# H16R7x_Backend.net
KiCad netlist of a schematic drawn in Altium Designer
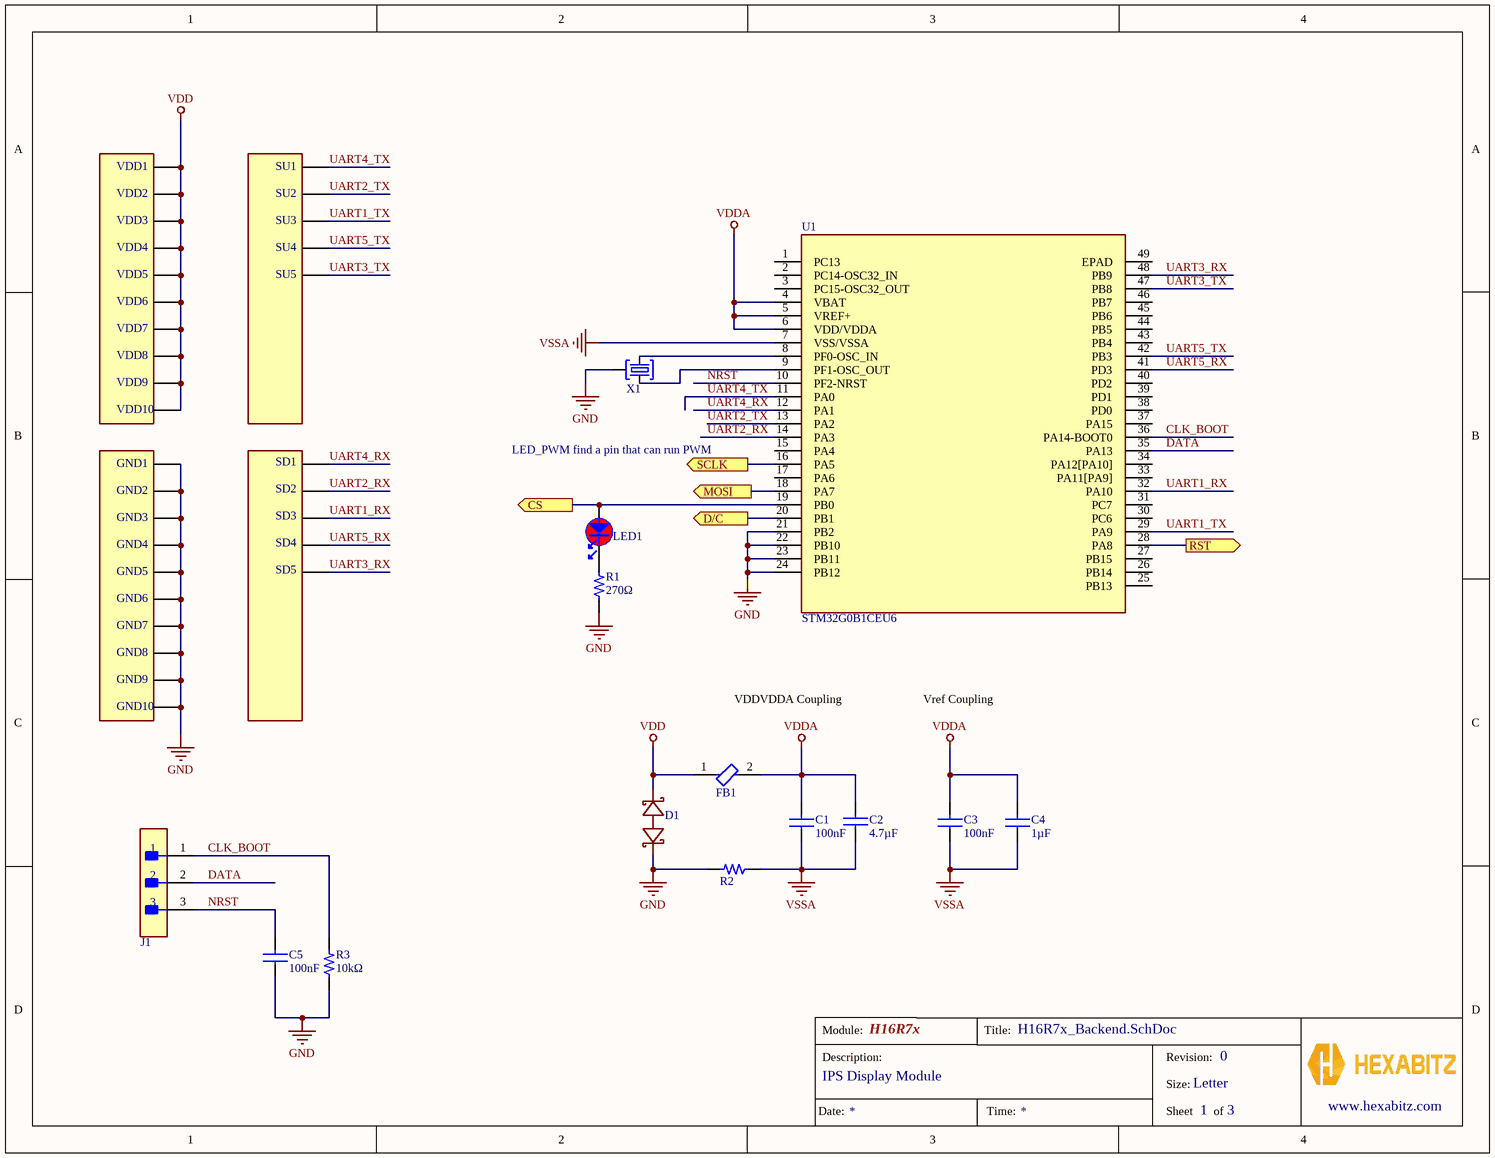
[diagram p0: H16R7x_Backend.SchDoc]

(export (version "E")
  (design (tool "Eeschema 10.0.6"))
  (components
    (comp (ref "C1")
      (value "100nF")
      (footprint "C0603")
      (fields
        (field (name "MANUFACTURER") "Samsung Electro-Mechanics")
        (field (name "MANUFACTURER PART NUMBER") "CL10B104KA8NNNC")
        (field (name "TOLERANCE") "10%")
      )
      (libsource (lib "Hexabitz Altium Library") (part "generic Capacitor"))
    )
    (comp (ref "C2")
      (value "4.7µF")
      (footprint "C0805")
      (fields
        (field (name "MANUFACTURER") "Samsung Electro-Mechanics")
        (field (name "MANUFACTURER PART NUMBER") "CL21X475KAQNNNE")
        (field (name "TOLERANCE") "10%")
      )
      (libsource (lib "Hexabitz Altium Library") (part "generic Capacitor"))
    )
    (comp (ref "C3")
      (value "100nF")
      (footprint "C0603")
      (fields
        (field (name "MANUFACTURER") "Samsung Electro-Mechanics")
        (field (name "MANUFACTURER PART NUMBER") "CL10B104KA8NNNC")
        (field (name "TOLERANCE") "10%")
      )
      (libsource (lib "Hexabitz Altium Library") (part "generic Capacitor"))
    )
    (comp (ref "C4")
      (value "1µF")
      (footprint "C0805")
      (description "Ceramic Capacitor, Ceramic, 16V, 10% +Tol, 10% -Tol, X7R, 15% TC, 1uF, Surface Mount, 0805")
      (fields
        (field (name "MANUFACTURER") "Yageo Group")
        (field (name "MANUFACTURER PART NUMBER") "CC0805KKX7R7BB105")
      )
      (libsource (lib "Hexabitz Altium Library") (part "generic Capacitor"))
    )
    (comp (ref "C5")
      (value "100nF")
      (footprint "C0603")
      (fields
        (field (name "MANUFACTURER") "Samsung Electro-Mechanics")
        (field (name "MANUFACTURER PART NUMBER") "CL10B104KA8NNNC")
        (field (name "TOLERANCE") "10%")
      )
      (libsource (lib "Hexabitz Altium Library") (part "generic Capacitor"))
    )
    (comp (ref "D1")
      (value "CDSOD323-T03SC")
      (footprint "SOD2513X114N")
      (description "A 3V, 350W, bi-directional, standard capacitance, SOD323 pkg TVS Diode ¦ Bourns CDSOD323-T03SC")
      (fields (field (name "MANUFACTURER") "Bourns"))
      (libsource (lib "Hexabitz Altium Library") (part "CDSOD323-T03SC"))
    )
    (comp (ref "FB1")
      (value "MMZ1608Y300B")
      (footprint "FP-MMZ1608-0_8-MFG")
      (description "Ferrite Beads 0603 30ohms 1500mA Signal Line AEC-Q200")
      (fields
        (field (name "MANUFACTURER") "TDK")
        (field (name "MANUFACTURER PART NUMBER") "MMZ1608Y300BTD25")
      )
      (libsource (lib "Hexabitz Altium Library") (part "MMZ1608Y300B"))
    )
    (comp (ref "GND1")
      (value "HEXABIT_UART_PORT")
      (footprint "HEXABIT_POWER_PORT_D")
      (libsource (lib "hexabitz_connectors.Library") (part "HEXABIT_POWER_PORT_D"))
    )
    (comp (ref "GND2")
      (value "HEXABIT_UART_PORT")
      (footprint "HEXABIT_POWER_PORT_D")
      (libsource (lib "hexabitz_connectors.Library") (part "HEXABIT_POWER_PORT_D"))
    )
    (comp (ref "GND3")
      (value "HEXABIT_UART_PORT")
      (footprint "HEXABIT_POWER_PORT_D_300R")
      (libsource (lib "hexabitz_connectors.Library") (part "HEXABIT_POWER_PORT_D_300R"))
    )
    (comp (ref "GND4")
      (value "HEXABIT_UART_PORT")
      (footprint "HEXABIT_POWER_PORT_D")
      (libsource (lib "hexabitz_connectors.Library") (part "HEXABIT_POWER_PORT_D"))
    )
    (comp (ref "GND5")
      (value "HEXABIT_UART_PORT")
      (footprint "HEXABIT_POWER_PORT_D")
      (libsource (lib "hexabitz_connectors.Library") (part "HEXABIT_POWER_PORT_D"))
    )
    (comp (ref "GND6")
      (value "HEXABIT_UART_PORT")
      (footprint "HEXABIT_POWER_PORT_D")
      (libsource (lib "hexabitz_connectors.Library") (part "HEXABIT_POWER_PORT_D"))
    )
    (comp (ref "GND7")
      (value "HEXABIT_UART_PORT")
      (footprint "HEXABIT_POWER_PORT_D")
      (libsource (lib "hexabitz_connectors.Library") (part "HEXABIT_POWER_PORT_D"))
    )
    (comp (ref "GND8")
      (value "HEXABIT_UART_PORT")
      (footprint "HEXABIT_POWER_PORT_D_300L")
      (libsource (lib "hexabitz_connectors.Library") (part "HEXABIT_POWER_PORT_D_300L"))
    )
    (comp (ref "GND9")
      (value "HEXABIT_UART_PORT")
      (footprint "HEXABIT_POWER_PORT_D")
      (libsource (lib "hexabitz_connectors.Library") (part "HEXABIT_POWER_PORT_D"))
    )
    (comp (ref "GND10")
      (value "HEXABIT_UART_PORT")
      (footprint "HEXABIT_POWER_PORT_D")
      (libsource (lib "hexabitz_connectors.Library") (part "HEXABIT_POWER_PORT_D"))
    )
    (comp (ref "J1")
      (value "TSW-103-14-G-S")
      (footprint "FP-TSW-103-14-G-S-MFG")
      (description "CONN HEADER VERT 3POS 2.54MM")
      (libsource (lib "Altium Content Vault") (part "cd3439d6ef35ae5d9b27ec4fdd3e828"))
    )
    (comp (ref "LED1")
      (value "VLMS1300-GS08")
      (footprint "FP-6_541-5092_01-4-MFG")
      (description "LED Uni-Color Super Red 639nm 2-Pin Chip 0603(1608Metric) T/R")
      (fields (field (name "MANUFACTURER") "Vishay Semiconductors"))
      (libsource (lib "Hexabitz Altium Library") (part "VLMS1300-GS08"))
    )
    (comp (ref "R1")
      (value "270Ω")
      (footprint "R0603")
      (description "Res Thick Film 0603 270 Ohm 5% 0.1W(1/10W) ±200ppm/C Pad SMD Automotive T/R")
      (fields
        (field (name "MANUFACTURER") "Panasonic")
        (field (name "MANUFACTURER PART NUMBER") "ERJ-3GEYJ271V")
      )
      (libsource (lib "") (part "generic Resistor_2"))
    )
    (comp (ref "R2")
      (value "Manufacturer Part Number")
      (footprint "R0603")
      (libsource (lib "") (part "generic Resistor_1"))
    )
    (comp (ref "R3")
      (value "10kΩ")
      (footprint "R0603")
      (description "100mW Thick Film Resistors ±100ppm/℃ ±1% 10kΩ 0603 Chip Resistor - Surface Mount ROHS")
      (fields
        (field (name "MANUFACTURER") "Yageo Group")
        (field (name "MANUFACTURER PART NUMBER") "RC0603FR-0710KL")
      )
      (libsource (lib "Hexabitz Altium Library") (part "generic Resistor"))
    )
    (comp (ref "SD1")
      (value "HEXABIT_UART_PORT")
      (footprint "HEXABIT_UART_PORT_D")
      (libsource (lib "hexabitz_connectors.Library") (part "HEXABIT_UART_PORT_D"))
    )
    (comp (ref "SD2")
      (value "HEXABIT_UART_PORT")
      (footprint "HEXABIT_UART_PORT_D")
      (libsource (lib "hexabitz_connectors.Library") (part "HEXABIT_UART_PORT_D"))
    )
    (comp (ref "SD3")
      (value "HEXABIT_UART_PORT")
      (footprint "HEXABIT_UART_PORT_D")
      (libsource (lib "hexabitz_connectors.Library") (part "HEXABIT_UART_PORT_D"))
    )
    (comp (ref "SD4")
      (value "HEXABIT_UART_PORT")
      (footprint "HEXABIT_UART_PORT_D")
      (libsource (lib "hexabitz_connectors.Library") (part "HEXABIT_UART_PORT_D"))
    )
    (comp (ref "SD5")
      (value "HEXABIT_UART_PORT")
      (footprint "HEXABIT_UART_PORT_D")
      (libsource (lib "hexabitz_connectors.Library") (part "HEXABIT_UART_PORT_D"))
    )
    (comp (ref "SU1")
      (value "HEXABIT_UART_PORT")
      (footprint "HEXABIT_UART_PORT_U")
      (libsource (lib "hexabitz_connectors.Library") (part "HEXABIT_UART_PORT_U"))
    )
    (comp (ref "SU2")
      (value "HEXABIT_UART_PORT")
      (footprint "HEXABIT_UART_PORT_U")
      (libsource (lib "hexabitz_connectors.Library") (part "HEXABIT_UART_PORT_U"))
    )
    (comp (ref "SU3")
      (value "HEXABIT_UART_PORT")
      (footprint "HEXABIT_UART_PORT_U")
      (libsource (lib "hexabitz_connectors.Library") (part "HEXABIT_UART_PORT_U"))
    )
    (comp (ref "SU4")
      (value "HEXABIT_UART_PORT")
      (footprint "HEXABIT_UART_PORT_U")
      (libsource (lib "hexabitz_connectors.Library") (part "HEXABIT_UART_PORT_U"))
    )
    (comp (ref "SU5")
      (value "HEXABIT_UART_PORT")
      (footprint "HEXABIT_UART_PORT_U")
      (libsource (lib "hexabitz_connectors.Library") (part "HEXABIT_UART_PORT_U"))
    )
    (comp (ref "U1")
      (value "STM32G0B1CEU6")
      (footprint "QFN50P700X700X65-49N-D")
      (description "MCU 32-bit ARM Cortex M0+ RISC 512KB Flash 1.8V/2.5V/3.3V 48-Pin UFQFPN EP Tray")
      (fields
        (field (name "MANUFACTURER") "STMicroelectronics")
        (field (name "MANUFACTURER PART NUMBER") "STM32G0B1CEU6")
      )
      (libsource (lib "Hexabitz Altium Library") (part "STM32G0B1CEU6"))
    )
    (comp (ref "VDD1")
      (value "HEXABIT_UART_PORT")
      (footprint "HEXABIT_POWER_PORT_U")
      (libsource (lib "hexabitz_connectors.Library") (part "HEXABIT_POWER_PORT_U"))
    )
    (comp (ref "VDD2")
      (value "HEXABIT_UART_PORT")
      (footprint "HEXABIT_POWER_PORT_U")
      (libsource (lib "hexabitz_connectors.Library") (part "HEXABIT_POWER_PORT_U"))
    )
    (comp (ref "VDD3")
      (value "HEXABIT_UART_PORT")
      (footprint "HEXABIT_POWER_PORT_U_300R")
      (libsource (lib "hexabitz_connectors.Library") (part "HEXABIT_POWER_PORT_U_300R"))
    )
    (comp (ref "VDD4")
      (value "HEXABIT_UART_PORT")
      (footprint "HEXABIT_POWER_PORT_U")
      (libsource (lib "hexabitz_connectors.Library") (part "HEXABIT_POWER_PORT_U"))
    )
    (comp (ref "VDD5")
      (value "HEXABIT_UART_PORT")
      (footprint "HEXABIT_POWER_PORT_U")
      (libsource (lib "hexabitz_connectors.Library") (part "HEXABIT_POWER_PORT_U"))
    )
    (comp (ref "VDD6")
      (value "HEXABIT_UART_PORT")
      (footprint "HEXABIT_POWER_PORT_U")
      (libsource (lib "hexabitz_connectors.Library") (part "HEXABIT_POWER_PORT_U"))
    )
    (comp (ref "VDD7")
      (value "HEXABIT_UART_PORT")
      (footprint "HEXABIT_POWER_PORT_U")
      (libsource (lib "hexabitz_connectors.Library") (part "HEXABIT_POWER_PORT_U"))
    )
    (comp (ref "VDD8")
      (value "HEXABIT_UART_PORT")
      (footprint "HEXABIT_POWER_PORT_U_300L")
      (libsource (lib "hexabitz_connectors.Library") (part "HEXABIT_POWER_PORT_U_300L"))
    )
    (comp (ref "VDD9")
      (value "HEXABIT_UART_PORT")
      (footprint "HEXABIT_POWER_PORT_U")
      (libsource (lib "hexabitz_connectors.Library") (part "HEXABIT_POWER_PORT_U"))
    )
    (comp (ref "VDD10")
      (value "HEXABIT_UART_PORT")
      (footprint "HEXABIT_POWER_PORT_U")
      (libsource (lib "hexabitz_connectors.Library") (part "HEXABIT_POWER_PORT_U"))
    )
    (comp (ref "X1")
      (value "CSTCE8M00G52Z-R0")
      (footprint "XTALL_CSTCE8M00G52")
      (description "Ceramic Resonator 8MHz ±0.5% (Tol) ±0.2% (Stability) 10pF 40Ohm 3-Pin CSMD T/R")
      (fields (field (name "MANUFACTURER") "Murata") (field (name "TOLERANCE") "0.5%"))
      (libsource (lib "Hexabitz Altium Library") (part "CSTCE8M00G52Z-R0"))
    )
  )
  (nets
    (net (code "1") (name "/CLK_BOOT") (class "Default")
      (node (ref "J1") (pin "1") (pinfunction "1_1") (pintype "passive"))
      (node (ref "R3") (pin "1") (pinfunction "1_1") (pintype "passive"))
      (node (ref "U1") (pin "36") (pinfunction "PA14-BOOT0_36") (pintype "passive"))
    )
    (net (code "2") (name "/CS") (class "Default")
      (node (ref "LED1") (pin "2") (pintype "passive"))
      (node (ref "U1") (pin "19") (pinfunction "PB0_19") (pintype "passive"))
    )
    (net (code "3") (name "/DATA") (class "Default")
      (node (ref "J1") (pin "2") (pinfunction "2_2") (pintype "passive"))
      (node (ref "U1") (pin "35") (pinfunction "PA13_35") (pintype "passive"))
    )
    (net (code "4") (name "/D{slash}C") (class "Default")
      (node (ref "U1") (pin "20") (pinfunction "PB1_20") (pintype "passive"))
    )
    (net (code "5") (name "/MOSI") (class "Default")
      (node (ref "U1") (pin "18") (pinfunction "PA7_18") (pintype "passive"))
    )
    (net (code "6") (name "/NRST") (class "Default")
      (node (ref "C5") (pin "2") (pinfunction "2_2") (pintype "passive"))
      (node (ref "J1") (pin "3") (pinfunction "3_3") (pintype "passive"))
      (node (ref "U1") (pin "10") (pinfunction "PF2-NRST_10") (pintype "passive"))
    )
    (net (code "7") (name "/RST") (class "Default")
      (node (ref "U1") (pin "28") (pinfunction "PA8_28") (pintype "passive"))
    )
    (net (code "8") (name "/SCLK") (class "Default")
      (node (ref "U1") (pin "16") (pinfunction "PA5_16") (pintype "passive"))
    )
    (net (code "9") (name "/UART1_RX") (class "Default")
      (node (ref "SD3") (pin "UART_D") (pinfunction "UART_D_UART_D") (pintype "passive"))
      (node (ref "U1") (pin "32") (pinfunction "PA10_32") (pintype "passive"))
    )
    (net (code "10") (name "/UART1_TX") (class "Default")
      (node (ref "SU3") (pin "UART_U") (pinfunction "UART_U_UART_U") (pintype "passive"))
      (node (ref "U1") (pin "29") (pinfunction "PA9_29") (pintype "passive"))
    )
    (net (code "11") (name "/UART2_RX") (class "Default")
      (node (ref "SD2") (pin "UART_D") (pinfunction "UART_D_UART_D") (pintype "passive"))
      (node (ref "U1") (pin "14") (pinfunction "PA3_14") (pintype "passive"))
    )
    (net (code "12") (name "/UART2_TX") (class "Default")
      (node (ref "SU2") (pin "UART_U") (pinfunction "UART_U_UART_U") (pintype "passive"))
      (node (ref "U1") (pin "13") (pinfunction "PA2_13") (pintype "passive"))
    )
    (net (code "13") (name "/UART3_RX") (class "Default")
      (node (ref "SD5") (pin "UART_D") (pinfunction "UART_D_UART_D") (pintype "passive"))
      (node (ref "U1") (pin "48") (pinfunction "PB9_48") (pintype "passive"))
    )
    (net (code "14") (name "/UART3_TX") (class "Default")
      (node (ref "SU5") (pin "UART_U") (pinfunction "UART_U_UART_U") (pintype "passive"))
      (node (ref "U1") (pin "47") (pinfunction "PB8_47") (pintype "passive"))
    )
    (net (code "15") (name "/UART4_RX") (class "Default")
      (node (ref "SD1") (pin "UART_D") (pinfunction "UART_D_UART_D") (pintype "passive"))
      (node (ref "U1") (pin "12") (pinfunction "PA1_12") (pintype "passive"))
    )
    (net (code "16") (name "/UART4_TX") (class "Default")
      (node (ref "SU1") (pin "UART_U") (pinfunction "UART_U_UART_U") (pintype "passive"))
      (node (ref "U1") (pin "11") (pinfunction "PA0_11") (pintype "passive"))
    )
    (net (code "17") (name "/UART5_RX") (class "Default")
      (node (ref "SD4") (pin "UART_D") (pinfunction "UART_D_UART_D") (pintype "passive"))
      (node (ref "U1") (pin "41") (pinfunction "PD3_41") (pintype "passive"))
    )
    (net (code "18") (name "/UART5_TX") (class "Default")
      (node (ref "SU4") (pin "UART_U") (pinfunction "UART_U_UART_U") (pintype "passive"))
      (node (ref "U1") (pin "42") (pinfunction "PB3_42") (pintype "passive"))
    )
    (net (code "19") (name "GND") (class "Default")
      (node (ref "C5") (pin "1") (pinfunction "1_1") (pintype "passive"))
      (node (ref "D1") (pin "1") (pinfunction "A_1") (pintype "passive"))
      (node (ref "GND1") (pin "Pwr_D") (pinfunction "Pwr_D_Pwr_D") (pintype "passive"))
      (node (ref "GND10") (pin "Pwr_D") (pinfunction "Pwr_D_Pwr_D") (pintype "passive"))
      (node (ref "GND2") (pin "Pwr_D") (pinfunction "Pwr_D_Pwr_D") (pintype "passive"))
      (node (ref "GND3") (pin "Pwr_D") (pinfunction "Pwr_D_Pwr_D") (pintype "passive"))
      (node (ref "GND4") (pin "Pwr_D") (pinfunction "Pwr_D_Pwr_D") (pintype "passive"))
      (node (ref "GND5") (pin "Pwr_D") (pinfunction "Pwr_D_Pwr_D") (pintype "passive"))
      (node (ref "GND6") (pin "Pwr_D") (pinfunction "Pwr_D_Pwr_D") (pintype "passive"))
      (node (ref "GND7") (pin "Pwr_D") (pinfunction "Pwr_D_Pwr_D") (pintype "passive"))
      (node (ref "GND8") (pin "Pwr_D") (pinfunction "Pwr_D_Pwr_D") (pintype "passive"))
      (node (ref "GND9") (pin "Pwr_D") (pinfunction "Pwr_D_Pwr_D") (pintype "passive"))
      (node (ref "R1") (pin "1") (pinfunction "1_1") (pintype "passive"))
      (node (ref "R2") (pin "1") (pinfunction "1_1") (pintype "passive"))
      (node (ref "R3") (pin "2") (pinfunction "2_2") (pintype "passive"))
      (node (ref "U1") (pin "21") (pinfunction "PB2_21") (pintype "passive"))
      (node (ref "U1") (pin "22") (pinfunction "PB10_22") (pintype "passive"))
      (node (ref "U1") (pin "23") (pinfunction "PB11_23") (pintype "passive"))
      (node (ref "U1") (pin "24") (pinfunction "PB12_24") (pintype "passive"))
      (node (ref "X1") (pin "P$2") (pinfunction "2_P$2") (pintype "passive"))
    )
    (net (code "20") (name "Net-(LED1-Pad1)") (class "Default")
      (node (ref "LED1") (pin "1") (pintype "passive"))
      (node (ref "R1") (pin "2") (pinfunction "2_2") (pintype "passive"))
    )
    (net (code "21") (name "Net-(U1-PF0-OSC_IN)") (class "Default")
      (node (ref "U1") (pin "8") (pinfunction "PF0-OSC_IN_8") (pintype "passive"))
      (node (ref "X1") (pin "P$3") (pinfunction "3_P$3") (pintype "passive"))
    )
    (net (code "22") (name "Net-(U1-PF1-OSC_OUT)") (class "Default")
      (node (ref "U1") (pin "9") (pinfunction "PF1-OSC_OUT_9") (pintype "passive"))
      (node (ref "X1") (pin "P$1") (pinfunction "1_P$1") (pintype "passive"))
    )
    (net (code "23") (name "VDD") (class "Default")
      (node (ref "D1") (pin "2") (pinfunction "C_2") (pintype "passive"))
      (node (ref "FB1") (pin "1") (pinfunction "1_1") (pintype "passive"))
      (node (ref "VDD1") (pin "Pwr_U") (pinfunction "Pwr_U_Pwr_U") (pintype "passive"))
      (node (ref "VDD10") (pin "Pwr_U") (pinfunction "Pwr_U_Pwr_U") (pintype "passive"))
      (node (ref "VDD2") (pin "Pwr_U") (pinfunction "Pwr_U_Pwr_U") (pintype "passive"))
      (node (ref "VDD3") (pin "Pwr_U") (pinfunction "Pwr_U_Pwr_U") (pintype "passive"))
      (node (ref "VDD4") (pin "Pwr_U") (pinfunction "Pwr_U_Pwr_U") (pintype "passive"))
      (node (ref "VDD5") (pin "Pwr_U") (pinfunction "Pwr_U_Pwr_U") (pintype "passive"))
      (node (ref "VDD6") (pin "Pwr_U") (pinfunction "Pwr_U_Pwr_U") (pintype "passive"))
      (node (ref "VDD7") (pin "Pwr_U") (pinfunction "Pwr_U_Pwr_U") (pintype "passive"))
      (node (ref "VDD8") (pin "Pwr_U") (pinfunction "Pwr_U_Pwr_U") (pintype "passive"))
      (node (ref "VDD9") (pin "Pwr_U") (pinfunction "Pwr_U_Pwr_U") (pintype "passive"))
    )
    (net (code "24") (name "VDDA") (class "Default")
      (node (ref "C1") (pin "2") (pinfunction "2_2") (pintype "passive"))
      (node (ref "C2") (pin "1") (pinfunction "1_1") (pintype "passive"))
      (node (ref "C3") (pin "2") (pinfunction "2_2") (pintype "passive"))
      (node (ref "C4") (pin "2") (pinfunction "2_2") (pintype "passive"))
      (node (ref "FB1") (pin "2") (pinfunction "2_2") (pintype "passive"))
      (node (ref "U1") (pin "4") (pinfunction "VBAT_4") (pintype "passive"))
      (node (ref "U1") (pin "5") (pinfunction "VREF+_5") (pintype "passive"))
      (node (ref "U1") (pin "6") (pinfunction "VDD/VDDA_6") (pintype "passive"))
    )
    (net (code "25") (name "VSSA") (class "Default")
      (node (ref "C1") (pin "1") (pinfunction "1_1") (pintype "passive"))
      (node (ref "C2") (pin "2") (pinfunction "2_2") (pintype "passive"))
      (node (ref "C3") (pin "1") (pinfunction "1_1") (pintype "passive"))
      (node (ref "C4") (pin "1") (pinfunction "1_1") (pintype "passive"))
      (node (ref "R2") (pin "2") (pinfunction "2_2") (pintype "passive"))
      (node (ref "U1") (pin "7") (pinfunction "VSS/VSSA_7") (pintype "passive"))
    )
    (net (code "26") (name "unconnected-(U1-EPAD-Pad49)") (class "Default")
      (node (ref "U1") (pin "49") (pinfunction "EPAD_49") (pintype "passive"))
    )
    (net (code "27") (name "unconnected-(U1-PA4-Pad15)") (class "Default")
      (node (ref "U1") (pin "15") (pinfunction "PA4_15") (pintype "passive"))
    )
    (net (code "28") (name "unconnected-(U1-PA6-Pad17)") (class "Default")
      (node (ref "U1") (pin "17") (pinfunction "PA6_17") (pintype "passive"))
    )
    (net (code "29") (name "unconnected-(U1-PA11[PA9]-Pad33)") (class "Default")
      (node (ref "U1") (pin "33") (pinfunction "PA11[PA9]_33") (pintype "passive"))
    )
    (net (code "30") (name "unconnected-(U1-PA12[PA10]-Pad34)") (class "Default")
      (node (ref "U1") (pin "34") (pinfunction "PA12[PA10]_34") (pintype "passive"))
    )
    (net (code "31") (name "unconnected-(U1-PA15-Pad37)") (class "Default")
      (node (ref "U1") (pin "37") (pinfunction "PA15_37") (pintype "passive"))
    )
    (net (code "32") (name "unconnected-(U1-PB4-Pad43)") (class "Default")
      (node (ref "U1") (pin "43") (pinfunction "PB4_43") (pintype "passive"))
    )
    (net (code "33") (name "unconnected-(U1-PB5-Pad44)") (class "Default")
      (node (ref "U1") (pin "44") (pinfunction "PB5_44") (pintype "passive"))
    )
    (net (code "34") (name "unconnected-(U1-PB6-Pad45)") (class "Default")
      (node (ref "U1") (pin "45") (pinfunction "PB6_45") (pintype "passive"))
    )
    (net (code "35") (name "unconnected-(U1-PB7-Pad46)") (class "Default")
      (node (ref "U1") (pin "46") (pinfunction "PB7_46") (pintype "passive"))
    )
    (net (code "36") (name "unconnected-(U1-PB13-Pad25)") (class "Default")
      (node (ref "U1") (pin "25") (pinfunction "PB13_25") (pintype "passive"))
    )
    (net (code "37") (name "unconnected-(U1-PB14-Pad26)") (class "Default")
      (node (ref "U1") (pin "26") (pinfunction "PB14_26") (pintype "passive"))
    )
    (net (code "38") (name "unconnected-(U1-PB15-Pad27)") (class "Default")
      (node (ref "U1") (pin "27") (pinfunction "PB15_27") (pintype "passive"))
    )
    (net (code "39") (name "unconnected-(U1-PC6-Pad30)") (class "Default")
      (node (ref "U1") (pin "30") (pinfunction "PC6_30") (pintype "passive"))
    )
    (net (code "40") (name "unconnected-(U1-PC7-Pad31)") (class "Default")
      (node (ref "U1") (pin "31") (pinfunction "PC7_31") (pintype "passive"))
    )
    (net (code "41") (name "unconnected-(U1-PC13-Pad1)") (class "Default")
      (node (ref "U1") (pin "1") (pinfunction "PC13_1") (pintype "passive"))
    )
    (net (code "42") (name "unconnected-(U1-PC14-OSC32_IN-Pad2)") (class "Default")
      (node (ref "U1") (pin "2") (pinfunction "PC14-OSC32_IN_2") (pintype "passive"))
    )
    (net (code "43") (name "unconnected-(U1-PC15-OSC32_OUT-Pad3)") (class "Default")
      (node (ref "U1") (pin "3") (pinfunction "PC15-OSC32_OUT_3") (pintype "passive"))
    )
    (net (code "44") (name "unconnected-(U1-PD0-Pad38)") (class "Default")
      (node (ref "U1") (pin "38") (pinfunction "PD0_38") (pintype "passive"))
    )
    (net (code "45") (name "unconnected-(U1-PD1-Pad39)") (class "Default")
      (node (ref "U1") (pin "39") (pinfunction "PD1_39") (pintype "passive"))
    )
    (net (code "46") (name "unconnected-(U1-PD2-Pad40)") (class "Default")
      (node (ref "U1") (pin "40") (pinfunction "PD2_40") (pintype "passive"))
    )
  )
)
